# K60.net
KiCad netlist of a schematic drawn in Altium Designer
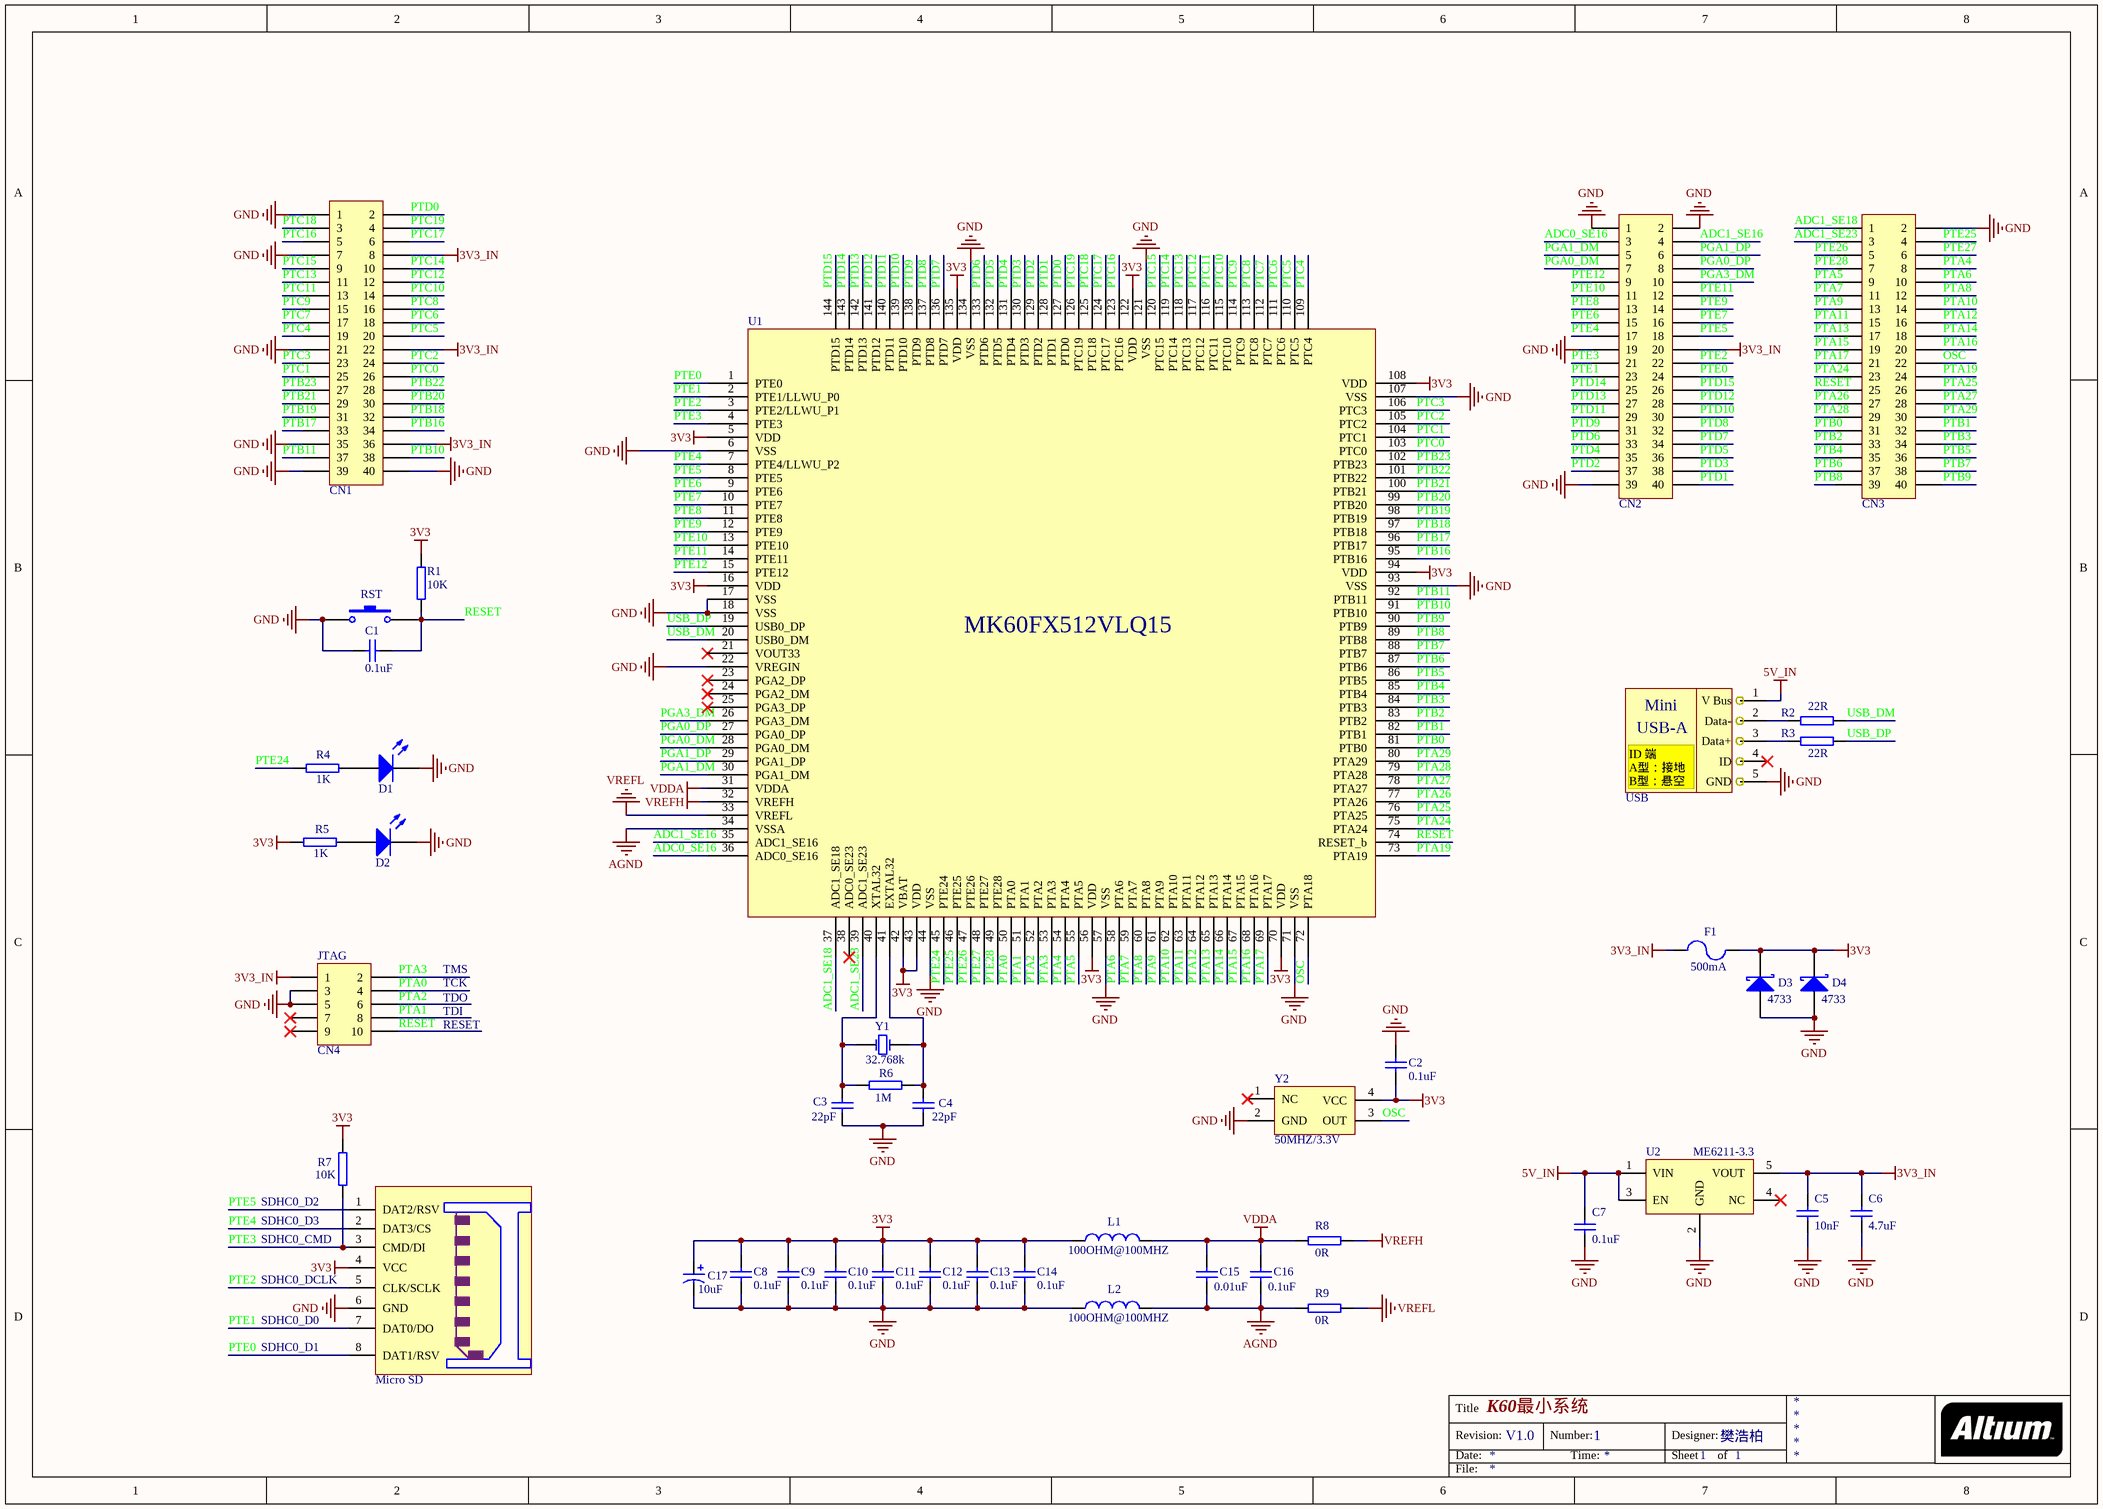
[diagram p0: K60最小系统.SchDoc]

(export (version "E")
  (design (tool "Eeschema 10.0.6"))
  (components
    (comp (ref "C1") (value "0.1uF") (footprint "CAP-0603") (libsource (lib "Connectors") (part "Cap")))
    (comp (ref "C2") (value "0.1uF") (footprint "CAP-0603") (libsource (lib "Connectors") (part "Cap")))
    (comp (ref "C3") (value "22pF") (footprint "CAP-0603") (libsource (lib "Connectors") (part "Cap")))
    (comp (ref "C4") (value "22pF") (footprint "CAP-0603") (libsource (lib "Connectors") (part "Cap")))
    (comp (ref "C5") (value "10nF") (footprint "CAP-0603") (libsource (lib "Connectors") (part "Cap")))
    (comp (ref "C6") (value "4.7uF") (footprint "CAP-0603") (libsource (lib "Connectors") (part "Cap")))
    (comp (ref "C7") (value "0.1uF") (footprint "CAP-0603") (libsource (lib "Connectors") (part "Cap")))
    (comp (ref "C8") (value "0.1uF") (footprint "CAP-0603") (libsource (lib "Connectors") (part "Cap")))
    (comp (ref "C9") (value "0.1uF") (footprint "CAP-0603") (libsource (lib "Connectors") (part "Cap")))
    (comp (ref "C10") (value "0.1uF") (footprint "CAP-0603") (libsource (lib "Connectors") (part "Cap")))
    (comp (ref "C11") (value "0.1uF") (footprint "CAP-0603") (libsource (lib "Connectors") (part "Cap")))
    (comp (ref "C12") (value "0.1uF") (footprint "CAP-0603") (libsource (lib "Connectors") (part "Cap")))
    (comp (ref "C13") (value "0.1uF") (footprint "CAP-0603") (libsource (lib "Connectors") (part "Cap")))
    (comp (ref "C14") (value "0.1uF") (footprint "CAP-0603") (libsource (lib "Connectors") (part "Cap")))
    (comp (ref "C15") (value "0.01uF") (footprint "CAP-0603") (libsource (lib "Connectors") (part "Cap")))
    (comp (ref "C16") (value "0.1uF") (footprint "CAP-0603") (libsource (lib "Connectors") (part "Cap")))
    (comp (ref "C17")
      (value "10uF")
      (footprint "CASE-A_3216-18")
      (libsource (lib "Connectors") (part "Cap-Pol_1"))
    )
    (comp (ref "CN1")
      (value "CON-20X2")
      (footprint "Pin-Header-2.00-Double-40")
      (libsource (lib "Connectors-Header") (part "CON-20X2"))
    )
    (comp (ref "CN2")
      (value "CON-20X2")
      (footprint "Pin-Header-2.00-Double-40")
      (libsource (lib "Connectors-Header") (part "CON-20X2"))
    )
    (comp (ref "CN3")
      (value "CON-20X2")
      (footprint "Pin-Header-2.00-Double-40")
      (libsource (lib "Connectors-Header") (part "CON-20X2"))
    )
    (comp (ref "CN4")
      (value "JTAG")
      (footprint "Pin-Header-2.54-Double-10")
      (libsource (lib "Connectors-Header") (part "CON-5X2"))
    )
    (comp (ref "D1") (value "LED") (footprint "LED-RED-0603") (libsource (lib "Connectors") (part "LED")))
    (comp (ref "D2") (value "LED") (footprint "LED-BLU-0603") (libsource (lib "Connectors") (part "LED")))
    (comp (ref "D3")
      (value "4733")
      (footprint "Diode-SMD-1206")
      (libsource (lib "Connectors") (part "Diode-Schottky"))
    )
    (comp (ref "D4")
      (value "4733")
      (footprint "Diode-SMD-1206")
      (libsource (lib "Connectors") (part "Diode-Schottky"))
    )
    (comp (ref "F1") (value "500mA") (footprint "Fuse-1206") (libsource (lib "Connectors") (part "Fuse")))
    (comp (ref "L1")
      (value "100OHM@100MHZ")
      (footprint "Chip Inductor-0603_160808")
      (libsource (lib "Connectors") (part "Inductor"))
    )
    (comp (ref "L2")
      (value "100OHM@100MHZ")
      (footprint "Chip Inductor-0603_160808")
      (libsource (lib "Connectors") (part "Inductor"))
    )
    (comp (ref "Micro SD")
      (value "SD")
      (footprint "Micro-SD")
      (libsource (lib "Connectors") (part "Micro-SD"))
    )
    (comp (ref "R1") (value "10K") (footprint "RES-0603") (libsource (lib "Connectors") (part "Res")))
    (comp (ref "R2") (value "22R") (footprint "RES-0603") (libsource (lib "Connectors") (part "Res")))
    (comp (ref "R3") (value "22R") (footprint "RES-0603") (libsource (lib "Connectors") (part "Res")))
    (comp (ref "R4") (value "1K") (footprint "RES-0603") (libsource (lib "Connectors") (part "Res")))
    (comp (ref "R5") (value "1K") (footprint "RES-0603") (libsource (lib "Connectors") (part "Res")))
    (comp (ref "R6") (value "1M") (footprint "RES-0603") (libsource (lib "Connectors") (part "Res")))
    (comp (ref "R7") (value "10K") (footprint "RES-0603") (libsource (lib "Connectors") (part "Res")))
    (comp (ref "R8") (value "0R") (footprint "RES-0603") (libsource (lib "Connectors") (part "Res")))
    (comp (ref "R9") (value "0R") (footprint "RES-0603") (libsource (lib "Connectors") (part "Res")))
    (comp (ref "RST") (value "Key") (footprint "SW-PB-2") (libsource (lib "Connectors") (part "Key-PB-2")))
    (comp (ref "U1")
      (value "MK60FX512VLQ15")
      (footprint "LQFP-144-20x20mm")
      (libsource (lib "Devices") (part "K60-144P"))
    )
    (comp (ref "U2")
      (value "ME6211-3.3")
      (footprint "SOT-23-5")
      (fields (field (name "PUBLISHER") "Altium Limited"))
      (libsource (lib "Devices") (part "LDO"))
    )
    (comp (ref "USB")
      (value "Mini-USB-A")
      (footprint "Mini-USB(a)-SMD")
      (libsource (lib "Connectors") (part "Mini-USB-A"))
    )
    (comp (ref "Y1")
      (value "32.768k")
      (footprint "XTAL-XYL-SMD")
      (libsource (lib "Connectors") (part "XTAL"))
    )
    (comp (ref "Y2")
      (value "50MHZ/3.3V")
      (footprint "XTAL-OSC-3225")
      (libsource (lib "Connectors") (part "XTAL-OSC"))
    )
  )
  (nets
    (net (code "1") (name "/ADC0_SE16") (class "Default")
      (node (ref "CN2") (pin "3") (pinfunction "3_3") (pintype "passive"))
      (node (ref "U1") (pin "36") (pinfunction "ADC0_SE16_36") (pintype "passive"))
    )
    (net (code "2") (name "/ADC1_SE16") (class "Default")
      (node (ref "CN2") (pin "4") (pinfunction "4_4") (pintype "passive"))
      (node (ref "U1") (pin "35") (pinfunction "ADC1_SE16_35") (pintype "passive"))
    )
    (net (code "3") (name "/ADC1_SE18") (class "Default")
      (node (ref "CN3") (pin "1") (pinfunction "1_1") (pintype "passive"))
      (node (ref "U1") (pin "37") (pinfunction "ADC1_SE18_37") (pintype "passive"))
    )
    (net (code "4") (name "/ADC1_SE23") (class "Default")
      (node (ref "CN3") (pin "3") (pinfunction "3_3") (pintype "passive"))
      (node (ref "U1") (pin "39") (pinfunction "ADC1_SE23_39") (pintype "passive"))
    )
    (net (code "5") (name "/OSC") (class "Default")
      (node (ref "CN3") (pin "22") (pinfunction "22_22") (pintype "passive"))
      (node (ref "U1") (pin "72") (pinfunction "PTA18_72") (pintype "passive"))
      (node (ref "Y2") (pin "3") (pinfunction "OUT_3") (pintype "passive"))
    )
    (net (code "6") (name "/PGA0_DM") (class "Default")
      (node (ref "CN2") (pin "7") (pinfunction "7_7") (pintype "passive"))
      (node (ref "U1") (pin "28") (pinfunction "PGA0_DM_28") (pintype "passive"))
    )
    (net (code "7") (name "/PGA0_DP") (class "Default")
      (node (ref "CN2") (pin "8") (pinfunction "8_8") (pintype "passive"))
      (node (ref "U1") (pin "27") (pinfunction "PGA0_DP_27") (pintype "passive"))
    )
    (net (code "8") (name "/PGA1_DM") (class "Default")
      (node (ref "CN2") (pin "5") (pinfunction "5_5") (pintype "passive"))
      (node (ref "U1") (pin "30") (pinfunction "PGA1_DM_30") (pintype "passive"))
    )
    (net (code "9") (name "/PGA1_DP") (class "Default")
      (node (ref "CN2") (pin "6") (pinfunction "6_6") (pintype "passive"))
      (node (ref "U1") (pin "29") (pinfunction "PGA1_DP_29") (pintype "passive"))
    )
    (net (code "10") (name "/PGA3_DM") (class "Default")
      (node (ref "CN2") (pin "10") (pinfunction "10_10") (pintype "passive"))
      (node (ref "U1") (pin "26") (pinfunction "PGA3_DM_26") (pintype "passive"))
    )
    (net (code "11") (name "/PTA0") (class "Default")
      (node (ref "CN4") (pin "4") (pinfunction "4_4") (pintype "passive"))
      (node (ref "U1") (pin "50") (pinfunction "PTA0_50") (pintype "passive"))
    )
    (net (code "12") (name "/PTA1") (class "Default")
      (node (ref "CN4") (pin "8") (pinfunction "8_8") (pintype "passive"))
      (node (ref "U1") (pin "51") (pinfunction "PTA1_51") (pintype "passive"))
    )
    (net (code "13") (name "/PTA2") (class "Default")
      (node (ref "CN4") (pin "6") (pinfunction "6_6") (pintype "passive"))
      (node (ref "U1") (pin "52") (pinfunction "PTA2_52") (pintype "passive"))
    )
    (net (code "14") (name "/PTA3") (class "Default")
      (node (ref "CN4") (pin "2") (pinfunction "2_2") (pintype "passive"))
      (node (ref "U1") (pin "53") (pinfunction "PTA3_53") (pintype "passive"))
    )
    (net (code "15") (name "/PTA4") (class "Default")
      (node (ref "CN3") (pin "8") (pinfunction "8_8") (pintype "passive"))
      (node (ref "U1") (pin "54") (pinfunction "PTA4_54") (pintype "passive"))
    )
    (net (code "16") (name "/PTA5") (class "Default")
      (node (ref "CN3") (pin "9") (pinfunction "9_9") (pintype "passive"))
      (node (ref "U1") (pin "55") (pinfunction "PTA5_55") (pintype "passive"))
    )
    (net (code "17") (name "/PTA6") (class "Default")
      (node (ref "CN3") (pin "10") (pinfunction "10_10") (pintype "passive"))
      (node (ref "U1") (pin "58") (pinfunction "PTA6_58") (pintype "passive"))
    )
    (net (code "18") (name "/PTA7") (class "Default")
      (node (ref "CN3") (pin "11") (pinfunction "11_11") (pintype "passive"))
      (node (ref "U1") (pin "59") (pinfunction "PTA7_59") (pintype "passive"))
    )
    (net (code "19") (name "/PTA8") (class "Default")
      (node (ref "CN3") (pin "12") (pinfunction "12_12") (pintype "passive"))
      (node (ref "U1") (pin "60") (pinfunction "PTA8_60") (pintype "passive"))
    )
    (net (code "20") (name "/PTA9") (class "Default")
      (node (ref "CN3") (pin "13") (pinfunction "13_13") (pintype "passive"))
      (node (ref "U1") (pin "61") (pinfunction "PTA9_61") (pintype "passive"))
    )
    (net (code "21") (name "/PTA10") (class "Default")
      (node (ref "CN3") (pin "14") (pinfunction "14_14") (pintype "passive"))
      (node (ref "U1") (pin "62") (pinfunction "PTA10_62") (pintype "passive"))
    )
    (net (code "22") (name "/PTA11") (class "Default")
      (node (ref "CN3") (pin "15") (pinfunction "15_15") (pintype "passive"))
      (node (ref "U1") (pin "63") (pinfunction "PTA11_63") (pintype "passive"))
    )
    (net (code "23") (name "/PTA12") (class "Default")
      (node (ref "CN3") (pin "16") (pinfunction "16_16") (pintype "passive"))
      (node (ref "U1") (pin "64") (pinfunction "PTA12_64") (pintype "passive"))
    )
    (net (code "24") (name "/PTA13") (class "Default")
      (node (ref "CN3") (pin "17") (pinfunction "17_17") (pintype "passive"))
      (node (ref "U1") (pin "65") (pinfunction "PTA13_65") (pintype "passive"))
    )
    (net (code "25") (name "/PTA14") (class "Default")
      (node (ref "CN3") (pin "18") (pinfunction "18_18") (pintype "passive"))
      (node (ref "U1") (pin "66") (pinfunction "PTA14_66") (pintype "passive"))
    )
    (net (code "26") (name "/PTA15") (class "Default")
      (node (ref "CN3") (pin "19") (pinfunction "19_19") (pintype "passive"))
      (node (ref "U1") (pin "67") (pinfunction "PTA15_67") (pintype "passive"))
    )
    (net (code "27") (name "/PTA16") (class "Default")
      (node (ref "CN3") (pin "20") (pinfunction "20_20") (pintype "passive"))
      (node (ref "U1") (pin "68") (pinfunction "PTA16_68") (pintype "passive"))
    )
    (net (code "28") (name "/PTA17") (class "Default")
      (node (ref "CN3") (pin "21") (pinfunction "21_21") (pintype "passive"))
      (node (ref "U1") (pin "69") (pinfunction "PTA17_69") (pintype "passive"))
    )
    (net (code "29") (name "/PTA19") (class "Default")
      (node (ref "CN3") (pin "24") (pinfunction "24_24") (pintype "passive"))
      (node (ref "U1") (pin "73") (pinfunction "PTA19_73") (pintype "passive"))
    )
    (net (code "30") (name "/PTA24") (class "Default")
      (node (ref "CN3") (pin "23") (pinfunction "23_23") (pintype "passive"))
      (node (ref "U1") (pin "75") (pinfunction "PTA24_75") (pintype "passive"))
    )
    (net (code "31") (name "/PTA25") (class "Default")
      (node (ref "CN3") (pin "26") (pinfunction "26_26") (pintype "passive"))
      (node (ref "U1") (pin "76") (pinfunction "PTA25_76") (pintype "passive"))
    )
    (net (code "32") (name "/PTA26") (class "Default")
      (node (ref "CN3") (pin "27") (pinfunction "27_27") (pintype "passive"))
      (node (ref "U1") (pin "77") (pinfunction "PTA26_77") (pintype "passive"))
    )
    (net (code "33") (name "/PTA27") (class "Default")
      (node (ref "CN3") (pin "28") (pinfunction "28_28") (pintype "passive"))
      (node (ref "U1") (pin "78") (pinfunction "PTA27_78") (pintype "passive"))
    )
    (net (code "34") (name "/PTA28") (class "Default")
      (node (ref "CN3") (pin "29") (pinfunction "29_29") (pintype "passive"))
      (node (ref "U1") (pin "79") (pinfunction "PTA28_79") (pintype "passive"))
    )
    (net (code "35") (name "/PTA29") (class "Default")
      (node (ref "CN3") (pin "30") (pinfunction "30_30") (pintype "passive"))
      (node (ref "U1") (pin "80") (pinfunction "PTA29_80") (pintype "passive"))
    )
    (net (code "36") (name "/PTB0") (class "Default")
      (node (ref "CN3") (pin "31") (pinfunction "31_31") (pintype "passive"))
      (node (ref "U1") (pin "81") (pinfunction "PTB0_81") (pintype "passive"))
    )
    (net (code "37") (name "/PTB1") (class "Default")
      (node (ref "CN3") (pin "32") (pinfunction "32_32") (pintype "passive"))
      (node (ref "U1") (pin "82") (pinfunction "PTB1_82") (pintype "passive"))
    )
    (net (code "38") (name "/PTB2") (class "Default")
      (node (ref "CN3") (pin "33") (pinfunction "33_33") (pintype "passive"))
      (node (ref "U1") (pin "83") (pinfunction "PTB2_83") (pintype "passive"))
    )
    (net (code "39") (name "/PTB3") (class "Default")
      (node (ref "CN3") (pin "34") (pinfunction "34_34") (pintype "passive"))
      (node (ref "U1") (pin "84") (pinfunction "PTB3_84") (pintype "passive"))
    )
    (net (code "40") (name "/PTB4") (class "Default")
      (node (ref "CN3") (pin "35") (pinfunction "35_35") (pintype "passive"))
      (node (ref "U1") (pin "85") (pinfunction "PTB4_85") (pintype "passive"))
    )
    (net (code "41") (name "/PTB5") (class "Default")
      (node (ref "CN3") (pin "36") (pinfunction "36_36") (pintype "passive"))
      (node (ref "U1") (pin "86") (pinfunction "PTB5_86") (pintype "passive"))
    )
    (net (code "42") (name "/PTB6") (class "Default")
      (node (ref "CN3") (pin "37") (pinfunction "37_37") (pintype "passive"))
      (node (ref "U1") (pin "87") (pinfunction "PTB6_87") (pintype "passive"))
    )
    (net (code "43") (name "/PTB7") (class "Default")
      (node (ref "CN3") (pin "38") (pinfunction "38_38") (pintype "passive"))
      (node (ref "U1") (pin "88") (pinfunction "PTB7_88") (pintype "passive"))
    )
    (net (code "44") (name "/PTB8") (class "Default")
      (node (ref "CN3") (pin "39") (pinfunction "39_39") (pintype "passive"))
      (node (ref "U1") (pin "89") (pinfunction "PTB8_89") (pintype "passive"))
    )
    (net (code "45") (name "/PTB9") (class "Default")
      (node (ref "CN3") (pin "40") (pinfunction "40_40") (pintype "passive"))
      (node (ref "U1") (pin "90") (pinfunction "PTB9_90") (pintype "passive"))
    )
    (net (code "46") (name "/PTB10") (class "Default")
      (node (ref "CN1") (pin "38") (pinfunction "38_38") (pintype "passive"))
      (node (ref "U1") (pin "91") (pinfunction "PTB10_91") (pintype "passive"))
    )
    (net (code "47") (name "/PTB11") (class "Default")
      (node (ref "CN1") (pin "37") (pinfunction "37_37") (pintype "passive"))
      (node (ref "U1") (pin "92") (pinfunction "PTB11_92") (pintype "passive"))
    )
    (net (code "48") (name "/PTB16") (class "Default")
      (node (ref "CN1") (pin "34") (pinfunction "34_34") (pintype "passive"))
      (node (ref "U1") (pin "95") (pinfunction "PTB16_95") (pintype "passive"))
    )
    (net (code "49") (name "/PTB17") (class "Default")
      (node (ref "CN1") (pin "33") (pinfunction "33_33") (pintype "passive"))
      (node (ref "U1") (pin "96") (pinfunction "PTB17_96") (pintype "passive"))
    )
    (net (code "50") (name "/PTB18") (class "Default")
      (node (ref "CN1") (pin "32") (pinfunction "32_32") (pintype "passive"))
      (node (ref "U1") (pin "97") (pinfunction "PTB18_97") (pintype "passive"))
    )
    (net (code "51") (name "/PTB19") (class "Default")
      (node (ref "CN1") (pin "31") (pinfunction "31_31") (pintype "passive"))
      (node (ref "U1") (pin "98") (pinfunction "PTB19_98") (pintype "passive"))
    )
    (net (code "52") (name "/PTB20") (class "Default")
      (node (ref "CN1") (pin "30") (pinfunction "30_30") (pintype "passive"))
      (node (ref "U1") (pin "99") (pinfunction "PTB20_99") (pintype "passive"))
    )
    (net (code "53") (name "/PTB21") (class "Default")
      (node (ref "CN1") (pin "29") (pinfunction "29_29") (pintype "passive"))
      (node (ref "U1") (pin "100") (pinfunction "PTB21_100") (pintype "passive"))
    )
    (net (code "54") (name "/PTB22") (class "Default")
      (node (ref "CN1") (pin "28") (pinfunction "28_28") (pintype "passive"))
      (node (ref "U1") (pin "101") (pinfunction "PTB22_101") (pintype "passive"))
    )
    (net (code "55") (name "/PTB23") (class "Default")
      (node (ref "CN1") (pin "27") (pinfunction "27_27") (pintype "passive"))
      (node (ref "U1") (pin "102") (pinfunction "PTB23_102") (pintype "passive"))
    )
    (net (code "56") (name "/PTC0") (class "Default")
      (node (ref "CN1") (pin "26") (pinfunction "26_26") (pintype "passive"))
      (node (ref "U1") (pin "103") (pinfunction "PTC0_103") (pintype "passive"))
    )
    (net (code "57") (name "/PTC1") (class "Default")
      (node (ref "CN1") (pin "25") (pinfunction "25_25") (pintype "passive"))
      (node (ref "U1") (pin "104") (pinfunction "PTC1_104") (pintype "passive"))
    )
    (net (code "58") (name "/PTC2") (class "Default")
      (node (ref "CN1") (pin "24") (pinfunction "24_24") (pintype "passive"))
      (node (ref "U1") (pin "105") (pinfunction "PTC2_105") (pintype "passive"))
    )
    (net (code "59") (name "/PTC3") (class "Default")
      (node (ref "CN1") (pin "23") (pinfunction "23_23") (pintype "passive"))
      (node (ref "U1") (pin "106") (pinfunction "PTC3_106") (pintype "passive"))
    )
    (net (code "60") (name "/PTC4") (class "Default")
      (node (ref "CN1") (pin "19") (pinfunction "19_19") (pintype "passive"))
      (node (ref "U1") (pin "109") (pinfunction "PTC4_109") (pintype "passive"))
    )
    (net (code "61") (name "/PTC5") (class "Default")
      (node (ref "CN1") (pin "20") (pinfunction "20_20") (pintype "passive"))
      (node (ref "U1") (pin "110") (pinfunction "PTC5_110") (pintype "passive"))
    )
    (net (code "62") (name "/PTC6") (class "Default")
      (node (ref "CN1") (pin "18") (pinfunction "18_18") (pintype "passive"))
      (node (ref "U1") (pin "111") (pinfunction "PTC6_111") (pintype "passive"))
    )
    (net (code "63") (name "/PTC7") (class "Default")
      (node (ref "CN1") (pin "17") (pinfunction "17_17") (pintype "passive"))
      (node (ref "U1") (pin "112") (pinfunction "PTC7_112") (pintype "passive"))
    )
    (net (code "64") (name "/PTC8") (class "Default")
      (node (ref "CN1") (pin "16") (pinfunction "16_16") (pintype "passive"))
      (node (ref "U1") (pin "113") (pinfunction "PTC8_113") (pintype "passive"))
    )
    (net (code "65") (name "/PTC9") (class "Default")
      (node (ref "CN1") (pin "15") (pinfunction "15_15") (pintype "passive"))
      (node (ref "U1") (pin "114") (pinfunction "PTC9_114") (pintype "passive"))
    )
    (net (code "66") (name "/PTC10") (class "Default")
      (node (ref "CN1") (pin "14") (pinfunction "14_14") (pintype "passive"))
      (node (ref "U1") (pin "115") (pinfunction "PTC10_115") (pintype "passive"))
    )
    (net (code "67") (name "/PTC11") (class "Default")
      (node (ref "CN1") (pin "13") (pinfunction "13_13") (pintype "passive"))
      (node (ref "U1") (pin "116") (pinfunction "PTC11_116") (pintype "passive"))
    )
    (net (code "68") (name "/PTC12") (class "Default")
      (node (ref "CN1") (pin "12") (pinfunction "12_12") (pintype "passive"))
      (node (ref "U1") (pin "117") (pinfunction "PTC12_117") (pintype "passive"))
    )
    (net (code "69") (name "/PTC13") (class "Default")
      (node (ref "CN1") (pin "11") (pinfunction "11_11") (pintype "passive"))
      (node (ref "U1") (pin "118") (pinfunction "PTC13_118") (pintype "passive"))
    )
    (net (code "70") (name "/PTC14") (class "Default")
      (node (ref "CN1") (pin "10") (pinfunction "10_10") (pintype "passive"))
      (node (ref "U1") (pin "119") (pinfunction "PTC14_119") (pintype "passive"))
    )
    (net (code "71") (name "/PTC15") (class "Default")
      (node (ref "CN1") (pin "9") (pinfunction "9_9") (pintype "passive"))
      (node (ref "U1") (pin "120") (pinfunction "PTC15_120") (pintype "passive"))
    )
    (net (code "72") (name "/PTC16") (class "Default")
      (node (ref "CN1") (pin "5") (pinfunction "5_5") (pintype "passive"))
      (node (ref "U1") (pin "123") (pinfunction "PTC16_123") (pintype "passive"))
    )
    (net (code "73") (name "/PTC17") (class "Default")
      (node (ref "CN1") (pin "6") (pinfunction "6_6") (pintype "passive"))
      (node (ref "U1") (pin "124") (pinfunction "PTC17_124") (pintype "passive"))
    )
    (net (code "74") (name "/PTC18") (class "Default")
      (node (ref "CN1") (pin "3") (pinfunction "3_3") (pintype "passive"))
      (node (ref "U1") (pin "125") (pinfunction "PTC18_125") (pintype "passive"))
    )
    (net (code "75") (name "/PTC19") (class "Default")
      (node (ref "CN1") (pin "4") (pinfunction "4_4") (pintype "passive"))
      (node (ref "U1") (pin "126") (pinfunction "PTC19_126") (pintype "passive"))
    )
    (net (code "76") (name "/PTD0") (class "Default")
      (node (ref "CN1") (pin "2") (pinfunction "2_2") (pintype "passive"))
      (node (ref "U1") (pin "127") (pinfunction "PTD0_127") (pintype "passive"))
    )
    (net (code "77") (name "/PTD1") (class "Default")
      (node (ref "CN2") (pin "40") (pinfunction "40_40") (pintype "passive"))
      (node (ref "U1") (pin "128") (pinfunction "PTD1_128") (pintype "passive"))
    )
    (net (code "78") (name "/PTD2") (class "Default")
      (node (ref "CN2") (pin "37") (pinfunction "37_37") (pintype "passive"))
      (node (ref "U1") (pin "129") (pinfunction "PTD2_129") (pintype "passive"))
    )
    (net (code "79") (name "/PTD3") (class "Default")
      (node (ref "CN2") (pin "38") (pinfunction "38_38") (pintype "passive"))
      (node (ref "U1") (pin "130") (pinfunction "PTD3_130") (pintype "passive"))
    )
    (net (code "80") (name "/PTD4") (class "Default")
      (node (ref "CN2") (pin "35") (pinfunction "35_35") (pintype "passive"))
      (node (ref "U1") (pin "131") (pinfunction "PTD4_131") (pintype "passive"))
    )
    (net (code "81") (name "/PTD5") (class "Default")
      (node (ref "CN2") (pin "36") (pinfunction "36_36") (pintype "passive"))
      (node (ref "U1") (pin "132") (pinfunction "PTD5_132") (pintype "passive"))
    )
    (net (code "82") (name "/PTD6") (class "Default")
      (node (ref "CN2") (pin "33") (pinfunction "33_33") (pintype "passive"))
      (node (ref "U1") (pin "133") (pinfunction "PTD6_133") (pintype "passive"))
    )
    (net (code "83") (name "/PTD7") (class "Default")
      (node (ref "CN2") (pin "34") (pinfunction "34_34") (pintype "passive"))
      (node (ref "U1") (pin "136") (pinfunction "PTD7_136") (pintype "passive"))
    )
    (net (code "84") (name "/PTD8") (class "Default")
      (node (ref "CN2") (pin "32") (pinfunction "32_32") (pintype "passive"))
      (node (ref "U1") (pin "137") (pinfunction "PTD8_137") (pintype "passive"))
    )
    (net (code "85") (name "/PTD9") (class "Default")
      (node (ref "CN2") (pin "31") (pinfunction "31_31") (pintype "passive"))
      (node (ref "U1") (pin "138") (pinfunction "PTD9_138") (pintype "passive"))
    )
    (net (code "86") (name "/PTD10") (class "Default")
      (node (ref "CN2") (pin "30") (pinfunction "30_30") (pintype "passive"))
      (node (ref "U1") (pin "139") (pinfunction "PTD10_139") (pintype "passive"))
    )
    (net (code "87") (name "/PTD11") (class "Default")
      (node (ref "CN2") (pin "29") (pinfunction "29_29") (pintype "passive"))
      (node (ref "U1") (pin "140") (pinfunction "PTD11_140") (pintype "passive"))
    )
    (net (code "88") (name "/PTD12") (class "Default")
      (node (ref "CN2") (pin "28") (pinfunction "28_28") (pintype "passive"))
      (node (ref "U1") (pin "141") (pinfunction "PTD12_141") (pintype "passive"))
    )
    (net (code "89") (name "/PTD13") (class "Default")
      (node (ref "CN2") (pin "27") (pinfunction "27_27") (pintype "passive"))
      (node (ref "U1") (pin "142") (pinfunction "PTD13_142") (pintype "passive"))
    )
    (net (code "90") (name "/PTD14") (class "Default")
      (node (ref "CN2") (pin "25") (pinfunction "25_25") (pintype "passive"))
      (node (ref "U1") (pin "143") (pinfunction "PTD14_143") (pintype "passive"))
    )
    (net (code "91") (name "/PTD15") (class "Default")
      (node (ref "CN2") (pin "26") (pinfunction "26_26") (pintype "passive"))
      (node (ref "U1") (pin "144") (pinfunction "PTD15_144") (pintype "passive"))
    )
    (net (code "92") (name "/PTE0") (class "Default")
      (node (ref "CN2") (pin "24") (pinfunction "24_24") (pintype "passive"))
      (node (ref "Micro SD") (pin "8") (pinfunction "DAT1/RSV_8") (pintype "passive"))
      (node (ref "U1") (pin "1") (pinfunction "PTE0_1") (pintype "passive"))
    )
    (net (code "93") (name "/PTE1") (class "Default")
      (node (ref "CN2") (pin "23") (pinfunction "23_23") (pintype "passive"))
      (node (ref "Micro SD") (pin "7") (pinfunction "DAT0/DO_7") (pintype "passive"))
      (node (ref "U1") (pin "2") (pinfunction "PTE1/LLWU_P0_2") (pintype "passive"))
    )
    (net (code "94") (name "/PTE2") (class "Default")
      (node (ref "CN2") (pin "22") (pinfunction "22_22") (pintype "passive"))
      (node (ref "Micro SD") (pin "5") (pinfunction "CLK/SCLK_5") (pintype "passive"))
      (node (ref "U1") (pin "3") (pinfunction "PTE2/LLWU_P1_3") (pintype "passive"))
    )
    (net (code "95") (name "/PTE3") (class "Default")
      (node (ref "CN2") (pin "21") (pinfunction "21_21") (pintype "passive"))
      (node (ref "Micro SD") (pin "3") (pinfunction "CMD/DI_3") (pintype "passive"))
      (node (ref "R7") (pin "1") (pinfunction "1_1") (pintype "passive"))
      (node (ref "U1") (pin "4") (pinfunction "PTE3_4") (pintype "passive"))
    )
    (net (code "96") (name "/PTE4") (class "Default")
      (node (ref "CN2") (pin "17") (pinfunction "17_17") (pintype "passive"))
      (node (ref "Micro SD") (pin "2") (pinfunction "DAT3/CS_2") (pintype "passive"))
      (node (ref "U1") (pin "7") (pinfunction "PTE4/LLWU_P2_7") (pintype "passive"))
    )
    (net (code "97") (name "/PTE5") (class "Default")
      (node (ref "CN2") (pin "18") (pinfunction "18_18") (pintype "passive"))
      (node (ref "Micro SD") (pin "1") (pinfunction "DAT2/RSV_1") (pintype "passive"))
      (node (ref "U1") (pin "8") (pinfunction "PTE5_8") (pintype "passive"))
    )
    (net (code "98") (name "/PTE6") (class "Default")
      (node (ref "CN2") (pin "15") (pinfunction "15_15") (pintype "passive"))
      (node (ref "U1") (pin "9") (pinfunction "PTE6_9") (pintype "passive"))
    )
    (net (code "99") (name "/PTE7") (class "Default")
      (node (ref "CN2") (pin "16") (pinfunction "16_16") (pintype "passive"))
      (node (ref "U1") (pin "10") (pinfunction "PTE7_10") (pintype "passive"))
    )
    (net (code "100") (name "/PTE8") (class "Default")
      (node (ref "CN2") (pin "13") (pinfunction "13_13") (pintype "passive"))
      (node (ref "U1") (pin "11") (pinfunction "PTE8_11") (pintype "passive"))
    )
    (net (code "101") (name "/PTE9") (class "Default")
      (node (ref "CN2") (pin "14") (pinfunction "14_14") (pintype "passive"))
      (node (ref "U1") (pin "12") (pinfunction "PTE9_12") (pintype "passive"))
    )
    (net (code "102") (name "/PTE10") (class "Default")
      (node (ref "CN2") (pin "11") (pinfunction "11_11") (pintype "passive"))
      (node (ref "U1") (pin "13") (pinfunction "PTE10_13") (pintype "passive"))
    )
    (net (code "103") (name "/PTE11") (class "Default")
      (node (ref "CN2") (pin "12") (pinfunction "12_12") (pintype "passive"))
      (node (ref "U1") (pin "14") (pinfunction "PTE11_14") (pintype "passive"))
    )
    (net (code "104") (name "/PTE12") (class "Default")
      (node (ref "CN2") (pin "9") (pinfunction "9_9") (pintype "passive"))
      (node (ref "U1") (pin "15") (pinfunction "PTE12_15") (pintype "passive"))
    )
    (net (code "105") (name "/PTE24") (class "Default")
      (node (ref "R4") (pin "2") (pinfunction "2_2") (pintype "passive"))
      (node (ref "U1") (pin "45") (pinfunction "PTE24_45") (pintype "passive"))
    )
    (net (code "106") (name "/PTE25") (class "Default")
      (node (ref "CN3") (pin "4") (pinfunction "4_4") (pintype "passive"))
      (node (ref "U1") (pin "46") (pinfunction "PTE25_46") (pintype "passive"))
    )
    (net (code "107") (name "/PTE26") (class "Default")
      (node (ref "CN3") (pin "5") (pinfunction "5_5") (pintype "passive"))
      (node (ref "U1") (pin "47") (pinfunction "PTE26_47") (pintype "passive"))
    )
    (net (code "108") (name "/PTE27") (class "Default")
      (node (ref "CN3") (pin "6") (pinfunction "6_6") (pintype "passive"))
      (node (ref "U1") (pin "48") (pinfunction "PTE27_48") (pintype "passive"))
    )
    (net (code "109") (name "/PTE28") (class "Default")
      (node (ref "CN3") (pin "7") (pinfunction "7_7") (pintype "passive"))
      (node (ref "U1") (pin "49") (pinfunction "PTE28_49") (pintype "passive"))
    )
    (net (code "110") (name "/RESET") (class "Default")
      (node (ref "C1") (pin "1") (pinfunction "1_1") (pintype "passive"))
      (node (ref "CN3") (pin "25") (pinfunction "25_25") (pintype "passive"))
      (node (ref "CN4") (pin "10") (pinfunction "10_10") (pintype "passive"))
      (node (ref "R1") (pin "1") (pinfunction "1_1") (pintype "passive"))
      (node (ref "RST") (pin "2") (pinfunction "2_2") (pintype "passive"))
      (node (ref "U1") (pin "74") (pinfunction "RESET_b_74") (pintype "passive"))
    )
    (net (code "111") (name "/USB_DM") (class "Default")
      (node (ref "R2") (pin "2") (pinfunction "2_2") (pintype "passive"))
      (node (ref "U1") (pin "20") (pinfunction "USB0_DM_20") (pintype "passive"))
    )
    (net (code "112") (name "/USB_DP") (class "Default")
      (node (ref "R3") (pin "2") (pinfunction "2_2") (pintype "passive"))
      (node (ref "U1") (pin "19") (pinfunction "USB0_DP_19") (pintype "passive"))
    )
    (net (code "113") (name "3V3") (class "Default")
      (node (ref "C10") (pin "2") (pinfunction "2_2") (pintype "passive"))
      (node (ref "C11") (pin "2") (pinfunction "2_2") (pintype "passive"))
      (node (ref "C12") (pin "2") (pinfunction "2_2") (pintype "passive"))
      (node (ref "C13") (pin "2") (pinfunction "2_2") (pintype "passive"))
      (node (ref "C14") (pin "2") (pinfunction "2_2") (pintype "passive"))
      (node (ref "C17") (pin "A") (pinfunction "A_A") (pintype "passive"))
      (node (ref "C2") (pin "1") (pinfunction "1_1") (pintype "passive"))
      (node (ref "C8") (pin "2") (pinfunction "2_2") (pintype "passive"))
      (node (ref "C9") (pin "2") (pinfunction "2_2") (pintype "passive"))
      (node (ref "D3") (pin "K") (pinfunction "K_K") (pintype "passive"))
      (node (ref "D4") (pin "K") (pinfunction "K_K") (pintype "passive"))
      (node (ref "F1") (pin "2") (pinfunction "2_2") (pintype "passive"))
      (node (ref "L1") (pin "1") (pinfunction "1_1") (pintype "passive"))
      (node (ref "Micro SD") (pin "4") (pinfunction "VCC_4") (pintype "passive"))
      (node (ref "R1") (pin "2") (pinfunction "2_2") (pintype "passive"))
      (node (ref "R5") (pin "2") (pinfunction "2_2") (pintype "passive"))
      (node (ref "R7") (pin "2") (pinfunction "2_2") (pintype "passive"))
      (node (ref "U1") (pin "108") (pinfunction "VDD_108") (pintype "passive"))
      (node (ref "U1") (pin "122") (pinfunction "VDD_122") (pintype "passive"))
      (node (ref "U1") (pin "135") (pinfunction "VDD_135") (pintype "passive"))
      (node (ref "U1") (pin "16") (pinfunction "VDD_16") (pintype "passive"))
      (node (ref "U1") (pin "42") (pinfunction "VBAT_42") (pintype "passive"))
      (node (ref "U1") (pin "43") (pinfunction "VDD_43") (pintype "passive"))
      (node (ref "U1") (pin "5") (pinfunction "VDD_5") (pintype "passive"))
      (node (ref "U1") (pin "56") (pinfunction "VDD_56") (pintype "passive"))
      (node (ref "U1") (pin "70") (pinfunction "VDD_70") (pintype "passive"))
      (node (ref "U1") (pin "94") (pinfunction "VDD_94") (pintype "passive"))
      (node (ref "Y2") (pin "4") (pinfunction "VCC_4") (pintype "passive"))
    )
    (net (code "114") (name "3V3_IN") (class "Default")
      (node (ref "C5") (pin "1") (pinfunction "1_1") (pintype "passive"))
      (node (ref "C6") (pin "1") (pinfunction "1_1") (pintype "passive"))
      (node (ref "CN1") (pin "22") (pinfunction "22_22") (pintype "passive"))
      (node (ref "CN1") (pin "36") (pinfunction "36_36") (pintype "passive"))
      (node (ref "CN1") (pin "8") (pinfunction "8_8") (pintype "passive"))
      (node (ref "CN2") (pin "20") (pinfunction "20_20") (pintype "passive"))
      (node (ref "CN4") (pin "1") (pinfunction "1_1") (pintype "passive"))
      (node (ref "F1") (pin "1") (pinfunction "1_1") (pintype "passive"))
      (node (ref "U2") (pin "5") (pinfunction "VOUT_5") (pintype "passive"))
    )
    (net (code "115") (name "5V_IN") (class "Default")
      (node (ref "C7") (pin "1") (pinfunction "1_1") (pintype "passive"))
      (node (ref "U2") (pin "1") (pinfunction "VIN_1") (pintype "passive"))
      (node (ref "U2") (pin "3") (pinfunction "EN_3") (pintype "passive"))
      (node (ref "USB") (pin "1") (pinfunction "V_Bus_1") (pintype "power_in"))
    )
    (net (code "116") (name "AGND") (class "Default")
      (node (ref "C15") (pin "1") (pinfunction "1_1") (pintype "passive"))
      (node (ref "C16") (pin "1") (pinfunction "1_1") (pintype "passive"))
      (node (ref "L2") (pin "2") (pinfunction "2_2") (pintype "passive"))
      (node (ref "R9") (pin "1") (pinfunction "1_1") (pintype "passive"))
      (node (ref "U1") (pin "34") (pinfunction "VSSA_34") (pintype "passive"))
    )
    (net (code "117") (name "GND") (class "Default")
      (node (ref "C1") (pin "2") (pinfunction "2_2") (pintype "passive"))
      (node (ref "C10") (pin "1") (pinfunction "1_1") (pintype "passive"))
      (node (ref "C11") (pin "1") (pinfunction "1_1") (pintype "passive"))
      (node (ref "C12") (pin "1") (pinfunction "1_1") (pintype "passive"))
      (node (ref "C13") (pin "1") (pinfunction "1_1") (pintype "passive"))
      (node (ref "C14") (pin "1") (pinfunction "1_1") (pintype "passive"))
      (node (ref "C17") (pin "K") (pinfunction "K_K") (pintype "passive"))
      (node (ref "C2") (pin "2") (pinfunction "2_2") (pintype "passive"))
      (node (ref "C3") (pin "1") (pinfunction "1_1") (pintype "passive"))
      (node (ref "C4") (pin "1") (pinfunction "1_1") (pintype "passive"))
      (node (ref "C5") (pin "2") (pinfunction "2_2") (pintype "passive"))
      (node (ref "C6") (pin "2") (pinfunction "2_2") (pintype "passive"))
      (node (ref "C7") (pin "2") (pinfunction "2_2") (pintype "passive"))
      (node (ref "C8") (pin "1") (pinfunction "1_1") (pintype "passive"))
      (node (ref "C9") (pin "1") (pinfunction "1_1") (pintype "passive"))
      (node (ref "CN1") (pin "1") (pinfunction "1_1") (pintype "passive"))
      (node (ref "CN1") (pin "21") (pinfunction "21_21") (pintype "passive"))
      (node (ref "CN1") (pin "35") (pinfunction "35_35") (pintype "passive"))
      (node (ref "CN1") (pin "39") (pinfunction "39_39") (pintype "passive"))
      (node (ref "CN1") (pin "40") (pinfunction "40_40") (pintype "passive"))
      (node (ref "CN1") (pin "7") (pinfunction "7_7") (pintype "passive"))
      (node (ref "CN2") (pin "1") (pinfunction "1_1") (pintype "passive"))
      (node (ref "CN2") (pin "19") (pinfunction "19_19") (pintype "passive"))
      (node (ref "CN2") (pin "2") (pinfunction "2_2") (pintype "passive"))
      (node (ref "CN2") (pin "39") (pinfunction "39_39") (pintype "passive"))
      (node (ref "CN3") (pin "2") (pinfunction "2_2") (pintype "passive"))
      (node (ref "CN4") (pin "3") (pinfunction "3_3") (pintype "passive"))
      (node (ref "CN4") (pin "5") (pinfunction "5_5") (pintype "passive"))
      (node (ref "D1") (pin "K") (pinfunction "2_K") (pintype "passive"))
      (node (ref "D2") (pin "K") (pinfunction "2_K") (pintype "passive"))
      (node (ref "D3") (pin "A") (pinfunction "A_A") (pintype "passive"))
      (node (ref "D4") (pin "A") (pinfunction "A_A") (pintype "passive"))
      (node (ref "L2") (pin "1") (pinfunction "1_1") (pintype "passive"))
      (node (ref "Micro SD") (pin "6") (pinfunction "GND_6") (pintype "passive"))
      (node (ref "RST") (pin "1") (pinfunction "1_1") (pintype "passive"))
      (node (ref "U1") (pin "107") (pinfunction "VSS_107") (pintype "passive"))
      (node (ref "U1") (pin "121") (pinfunction "VSS_121") (pintype "passive"))
      (node (ref "U1") (pin "134") (pinfunction "VSS_134") (pintype "passive"))
      (node (ref "U1") (pin "17") (pinfunction "VSS_17") (pintype "passive"))
      (node (ref "U1") (pin "18") (pinfunction "VSS_18") (pintype "passive"))
      (node (ref "U1") (pin "22") (pinfunction "VREGIN_22") (pintype "passive"))
      (node (ref "U1") (pin "44") (pinfunction "VSS_44") (pintype "passive"))
      (node (ref "U1") (pin "57") (pinfunction "VSS_57") (pintype "passive"))
      (node (ref "U1") (pin "6") (pinfunction "VSS_6") (pintype "passive"))
      (node (ref "U1") (pin "71") (pinfunction "VSS_71") (pintype "passive"))
      (node (ref "U1") (pin "93") (pinfunction "VSS_93") (pintype "passive"))
      (node (ref "U2") (pin "2") (pinfunction "GND_2") (pintype "passive"))
      (node (ref "USB") (pin "5") (pinfunction "GND_5") (pintype "passive"))
      (node (ref "Y2") (pin "2") (pinfunction "GND_2") (pintype "passive"))
    )
    (net (code "118") (name "Net-(D1-1)") (class "Default")
      (node (ref "D1") (pin "A") (pinfunction "1_A") (pintype "passive"))
      (node (ref "R4") (pin "1") (pinfunction "1_1") (pintype "passive"))
    )
    (net (code "119") (name "Net-(D2-1)") (class "Default")
      (node (ref "D2") (pin "A") (pinfunction "1_A") (pintype "passive"))
      (node (ref "R5") (pin "1") (pinfunction "1_1") (pintype "passive"))
    )
    (net (code "120") (name "Net-(U1-EXTAL32)") (class "Default")
      (node (ref "C4") (pin "2") (pinfunction "2_2") (pintype "passive"))
      (node (ref "R6") (pin "1") (pinfunction "1_1") (pintype "passive"))
      (node (ref "U1") (pin "41") (pinfunction "EXTAL32_41") (pintype "passive"))
      (node (ref "Y1") (pin "3") (pinfunction "OSC2_3") (pintype "passive"))
    )
    (net (code "121") (name "Net-(U1-XTAL32)") (class "Default")
      (node (ref "C3") (pin "2") (pinfunction "2_2") (pintype "passive"))
      (node (ref "R6") (pin "2") (pinfunction "2_2") (pintype "passive"))
      (node (ref "U1") (pin "40") (pinfunction "XTAL32_40") (pintype "passive"))
      (node (ref "Y1") (pin "1") (pinfunction "OSC1_1") (pintype "passive"))
    )
    (net (code "122") (name "Net-(USB-Data+)") (class "Default")
      (node (ref "R3") (pin "1") (pinfunction "1_1") (pintype "passive"))
      (node (ref "USB") (pin "3") (pinfunction "Data+_3") (pintype "passive"))
    )
    (net (code "123") (name "Net-(USB-Data-)") (class "Default")
      (node (ref "R2") (pin "1") (pinfunction "1_1") (pintype "passive"))
      (node (ref "USB") (pin "2") (pinfunction "Data-_2") (pintype "passive"))
    )
    (net (code "124") (name "VDDA") (class "Default")
      (node (ref "C15") (pin "2") (pinfunction "2_2") (pintype "passive"))
      (node (ref "C16") (pin "2") (pinfunction "2_2") (pintype "passive"))
      (node (ref "L1") (pin "2") (pinfunction "2_2") (pintype "passive"))
      (node (ref "R8") (pin "1") (pinfunction "1_1") (pintype "passive"))
      (node (ref "U1") (pin "31") (pinfunction "VDDA_31") (pintype "passive"))
    )
    (net (code "125") (name "VREFH") (class "Default")
      (node (ref "R8") (pin "2") (pinfunction "2_2") (pintype "passive"))
      (node (ref "U1") (pin "32") (pinfunction "VREFH_32") (pintype "passive"))
    )
    (net (code "126") (name "VREFL") (class "Default")
      (node (ref "R9") (pin "2") (pinfunction "2_2") (pintype "passive"))
      (node (ref "U1") (pin "33") (pinfunction "VREFL_33") (pintype "passive"))
    )
    (net (code "127") (name "unconnected-(CN4-Pad7)") (class "Default")
      (node (ref "CN4") (pin "7") (pinfunction "7_7") (pintype "passive+no_connect"))
    )
    (net (code "128") (name "unconnected-(CN4-Pad9)") (class "Default")
      (node (ref "CN4") (pin "9") (pinfunction "9_9") (pintype "passive+no_connect"))
    )
    (net (code "129") (name "unconnected-(U1-ADC0_SE23-Pad38)") (class "Default")
      (node (ref "U1") (pin "38") (pinfunction "ADC0_SE23_38") (pintype "passive+no_connect"))
    )
    (net (code "130") (name "unconnected-(U1-PGA2_DM-Pad24)") (class "Default")
      (node (ref "U1") (pin "24") (pinfunction "PGA2_DM_24") (pintype "passive+no_connect"))
    )
    (net (code "131") (name "unconnected-(U1-PGA2_DP-Pad23)") (class "Default")
      (node (ref "U1") (pin "23") (pinfunction "PGA2_DP_23") (pintype "passive+no_connect"))
    )
    (net (code "132") (name "unconnected-(U1-PGA3_DP-Pad25)") (class "Default")
      (node (ref "U1") (pin "25") (pinfunction "PGA3_DP_25") (pintype "passive+no_connect"))
    )
    (net (code "133") (name "unconnected-(U1-VOUT33-Pad21)") (class "Default")
      (node (ref "U1") (pin "21") (pinfunction "VOUT33_21") (pintype "passive+no_connect"))
    )
    (net (code "134") (name "unconnected-(U2-NC-Pad4)") (class "Default")
      (node (ref "U2") (pin "4") (pinfunction "NC_4") (pintype "passive+no_connect"))
    )
    (net (code "135") (name "unconnected-(USB-ID-Pad4)") (class "Default")
      (node (ref "USB") (pin "4") (pinfunction "ID_4") (pintype "passive+no_connect"))
    )
    (net (code "136") (name "unconnected-(Y2-NC-Pad1)") (class "Default")
      (node (ref "Y2") (pin "1") (pinfunction "NC_1") (pintype "passive+no_connect"))
    )
  )
)
